# IsoSPI_V0_1.net
KiCad netlist of a schematic drawn in Altium Designer
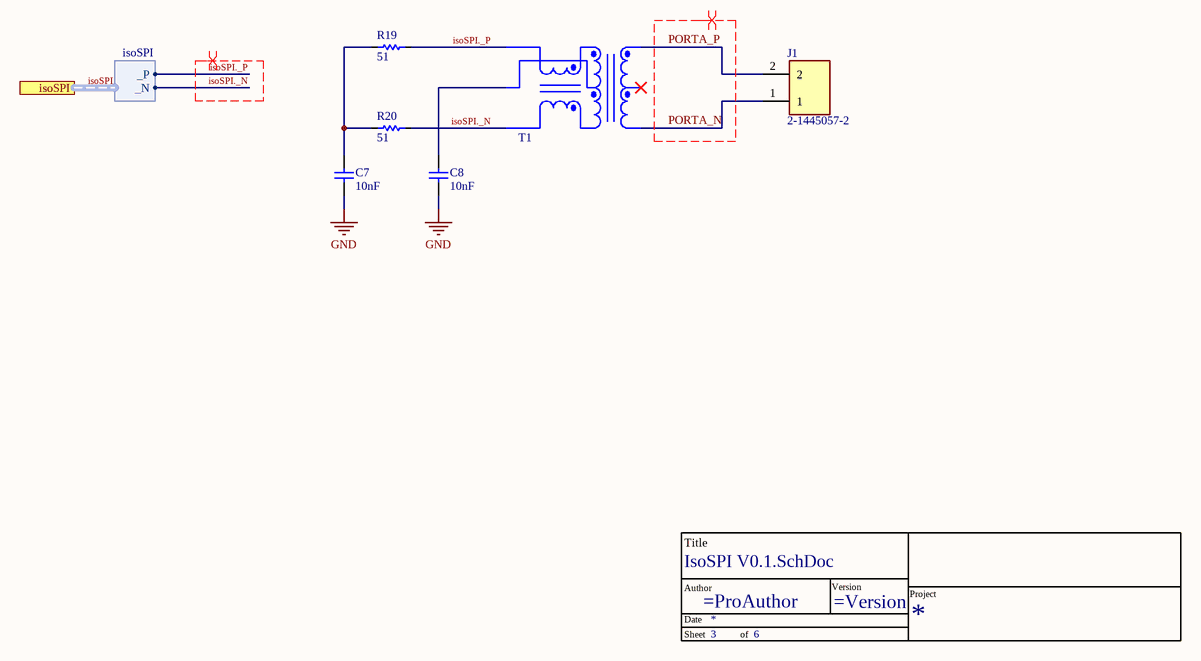
[diagram p0: IsoSPI V0.1.SchDoc]

(export (version "E")
  (design (tool "Eeschema 10.0.6"))
  (components
    (comp (ref "*") (value "TitleBlock") (libsource (lib "SchematicLib") (part "TitleBlock")))
    (comp (ref "C7")
      (value "10nF")
      (footprint "C-0402")
      (description "Capacitor")
      (fields (field (name "Comment") "C"))
      (libsource (lib "Passives") (part "Capacitor"))
    )
    (comp (ref "C8")
      (value "10nF")
      (footprint "C-0402")
      (description "Capacitor")
      (fields (field (name "Comment") "C"))
      (libsource (lib "Passives") (part "Capacitor"))
    )
    (comp (ref "J1")
      (value "2-1445057-2")
      (footprint "TE_2-1445057-2")
      (description "CONN HEADER 3MM 2POS R/A TIN SMD")
      (fields (field (name "MF") "{'manufacturer': u'TE Connectivity'}"))
      (libsource (lib "SnapEDA_Library") (part "2-1445057-2"))
    )
    (comp (ref "R19")
      (value "51")
      (footprint "R_0402")
      (description "Resistor")
      (libsource (lib "Passives") (part "Resistor"))
    )
    (comp (ref "R20")
      (value "51")
      (footprint "R_0402")
      (description "Resistor")
      (libsource (lib "Passives") (part "Resistor"))
    )
    (comp (ref "T1")
      (value "SM91502ALE")
      (footprint "SM91502ALE")
      (description "BMS XFORMER 1-CH 1000V AECQ +125")
      (fields (field (name "MANUFACTURER") "Bourns"))
      (libsource (lib "SchematicLib") (part "SM91502ALE"))
    )
  )
  (nets
    (net (code "2") (name "/PORTA_N") (class "Default")
      (node (ref "J1") (pin "1") (pinfunction "1_1") (pintype "passive"))
      (node (ref "T1") (pin "3") (pinfunction "3_3") (pintype "passive"))
    )
    (net (code "3") (name "/PORTA_P") (class "Default")
      (node (ref "J1") (pin "2") (pinfunction "2_2") (pintype "passive"))
      (node (ref "T1") (pin "1") (pinfunction "1_1") (pintype "passive"))
    )
    (net (code "4") (name "/isoSPI._N") (class "Default")
      (node (ref "R20") (pin "2") (pinfunction "2_2") (pintype "passive"))
      (node (ref "T1") (pin "4") (pinfunction "4_4") (pintype "passive"))
    )
    (net (code "5") (name "/isoSPI._P") (class "Default")
      (node (ref "R19") (pin "2") (pinfunction "2_2") (pintype "passive"))
      (node (ref "T1") (pin "6") (pinfunction "6_6") (pintype "passive"))
    )
    (net (code "7") (name "GND") (class "Default")
      (node (ref "C7") (pin "1") (pinfunction "1_1") (pintype "passive"))
      (node (ref "C8") (pin "1") (pinfunction "1_1") (pintype "passive"))
    )
    (net (code "8") (name "Net-(C7-Pad2)") (class "Default")
      (node (ref "C7") (pin "2") (pinfunction "2_2") (pintype "passive"))
      (node (ref "R19") (pin "1") (pinfunction "1_1") (pintype "passive"))
      (node (ref "R20") (pin "1") (pinfunction "1_1") (pintype "passive"))
    )
    (net (code "9") (name "Net-(C8-Pad2)") (class "Default")
      (node (ref "C8") (pin "2") (pinfunction "2_2") (pintype "passive"))
      (node (ref "T1") (pin "5") (pinfunction "5_5") (pintype "passive"))
    )
    (net (code "10") (name "unconnected-(T1-Pad2)") (class "Default")
      (node (ref "T1") (pin "2") (pinfunction "2_2") (pintype "passive+no_connect"))
    )
  )
)
